# RS485_RS232_Sheet.net
KiCad netlist of a schematic drawn in Altium Designer
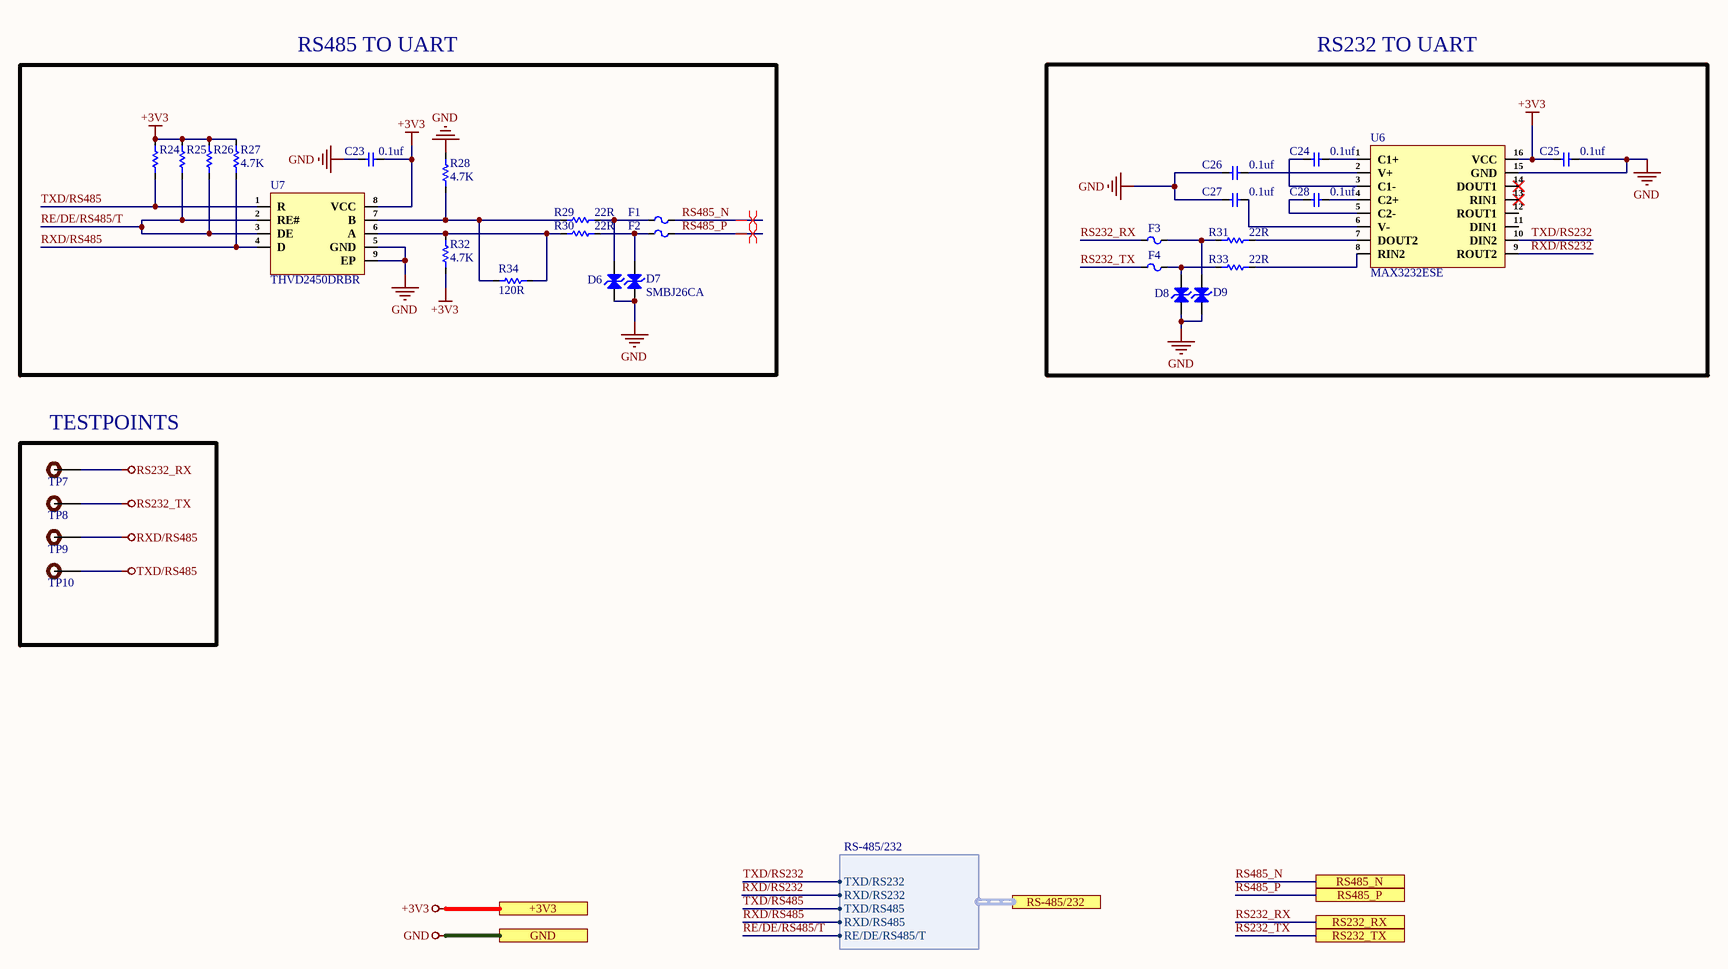
[diagram p0: RS485_RS232_Sheet.SchDoc]

(export (version "E")
  (design (tool "Eeschema 10.0.6"))
  (components
    (comp (ref "C23")
      (value "0.1uf")
      (footprint "Cap-0402")
      (description "CAP CER 0.1UF 100V X5R 0402")
      (fields
        (field (name "MANUFACTURER") "Murata")
        (field (name "MANUFACTURER PART NUMBER") "GRM155R62A104KE14D")
      )
      (libsource (lib "eSpark Libraries") (part "GRM155R62A104KE14D"))
    )
    (comp (ref "C24")
      (value "0.1uf")
      (footprint "Cap-0402")
      (description "CAP CER 0.1UF 100V X5R 0402")
      (fields
        (field (name "MANUFACTURER") "Murata")
        (field (name "MANUFACTURER PART NUMBER") "GRM155R62A104KE14D")
      )
      (libsource (lib "eSpark Libraries") (part "GRM155R62A104KE14D"))
    )
    (comp (ref "C25")
      (value "0.1uf")
      (footprint "Cap-0402")
      (description "CAP CER 0.1UF 100V X5R 0402")
      (fields
        (field (name "MANUFACTURER") "Murata")
        (field (name "MANUFACTURER PART NUMBER") "GRM155R62A104KE14D")
      )
      (libsource (lib "eSpark Libraries") (part "GRM155R62A104KE14D"))
    )
    (comp (ref "C26")
      (value "0.1uf")
      (footprint "Cap-0402")
      (description "CAP CER 0.1UF 100V X5R 0402")
      (fields
        (field (name "MANUFACTURER") "Murata")
        (field (name "MANUFACTURER PART NUMBER") "GRM155R62A104KE14D")
      )
      (libsource (lib "eSpark Libraries") (part "GRM155R62A104KE14D"))
    )
    (comp (ref "C27")
      (value "0.1uf")
      (footprint "Cap-0402")
      (description "CAP CER 0.1UF 100V X5R 0402")
      (fields
        (field (name "MANUFACTURER") "Murata")
        (field (name "MANUFACTURER PART NUMBER") "GRM155R62A104KE14D")
      )
      (libsource (lib "eSpark Libraries") (part "GRM155R62A104KE14D"))
    )
    (comp (ref "C28")
      (value "0.1uf")
      (footprint "Cap-0402")
      (description "CAP CER 0.1UF 100V X5R 0402")
      (fields
        (field (name "MANUFACTURER") "Murata")
        (field (name "MANUFACTURER PART NUMBER") "GRM155R62A104KE14D")
      )
      (libsource (lib "eSpark Libraries") (part "GRM155R62A104KE14D"))
    )
    (comp (ref "D6")
      (value "SMBJ26CA")
      (footprint "SMB Bi Directional")
      (description "SMB(DO-214AA) TVS ROHS")
      (fields (field (name "MANUFACTURER") "MSKSEMI") (field (name "LCSC PART NUMBER") "C5331111"))
      (libsource (lib "eSpark Libraries") (part "SMBJ26CA"))
    )
    (comp (ref "D7")
      (value "SMBJ26CA")
      (footprint "SMB Bi Directional")
      (description "SMB(DO-214AA) TVS ROHS")
      (fields (field (name "MANUFACTURER") "MSKSEMI") (field (name "LCSC PART NUMBER") "C5331111"))
      (libsource (lib "eSpark Libraries") (part "SMBJ26CA"))
    )
    (comp (ref "D8")
      (value "SMBJ26CA")
      (footprint "SMB Bi Directional")
      (description "SMB(DO-214AA) TVS ROHS")
      (fields (field (name "MANUFACTURER") "MSKSEMI") (field (name "LCSC PART NUMBER") "C5331111"))
      (libsource (lib "eSpark Libraries") (part "SMBJ26CA"))
    )
    (comp (ref "D9")
      (value "SMBJ26CA")
      (footprint "SMB Bi Directional")
      (description "SMB(DO-214AA) TVS ROHS")
      (fields (field (name "MANUFACTURER") "MSKSEMI") (field (name "LCSC PART NUMBER") "C5331111"))
      (libsource (lib "eSpark Libraries") (part "SMBJ26CA"))
    )
    (comp (ref "F1")
      (value "SMD0805P020TF")
      (footprint "Fuse-0805")
      (description "9V 200mA 100A 500mA 0805 Resettable Fuses ROHS")
      (fields (field (name "MANUFACTURER") "RUILON") (field (name "LCSC PART NUMBER") "C20976"))
      (libsource (lib "eSpark_centralized_Library(2022)") (part "SMD0805P020TF"))
    )
    (comp (ref "F2")
      (value "SMD0805P020TF")
      (footprint "Fuse-0805")
      (description "9V 200mA 100A 500mA 0805 Resettable Fuses ROHS")
      (fields (field (name "MANUFACTURER") "RUILON") (field (name "LCSC PART NUMBER") "C20976"))
      (libsource (lib "eSpark_centralized_Library(2022)") (part "SMD0805P020TF"))
    )
    (comp (ref "F3")
      (value "SMD0805P020TF")
      (footprint "Fuse-0805")
      (description "9V 200mA 100A 500mA 0805 Resettable Fuses ROHS")
      (fields (field (name "MANUFACTURER") "RUILON") (field (name "LCSC PART NUMBER") "C20976"))
      (libsource (lib "eSpark Libraries") (part "SMD0805P020TF"))
    )
    (comp (ref "F4")
      (value "SMD0805P020TF")
      (footprint "Fuse-0805")
      (description "9V 200mA 100A 500mA 0805 Resettable Fuses ROHS")
      (fields (field (name "MANUFACTURER") "RUILON") (field (name "LCSC PART NUMBER") "C20976"))
      (libsource (lib "eSpark Libraries") (part "SMD0805P020TF"))
    )
    (comp (ref "R24")
      (value "4.7K")
      (footprint "Res-0402")
      (description "RES 4.7K OHM 1% 1/16W 0402")
      (fields
        (field (name "MANUFACTURER") "Yageo")
        (field (name "MANUFACTURER PART NUMBER") "RC0402FR-074K7L")
      )
      (libsource (lib "eSpark Libraries") (part "RC0402FR-074K7L"))
    )
    (comp (ref "R25")
      (value "4.7K")
      (footprint "Res-0402")
      (description "RES 4.7K OHM 1% 1/16W 0402")
      (fields
        (field (name "MANUFACTURER") "Yageo")
        (field (name "MANUFACTURER PART NUMBER") "RC0402FR-074K7L")
      )
      (libsource (lib "eSpark Libraries") (part "RC0402FR-074K7L"))
    )
    (comp (ref "R26")
      (value "4.7K")
      (footprint "Res-0402")
      (description "RES 4.7K OHM 1% 1/16W 0402")
      (fields
        (field (name "MANUFACTURER") "Yageo")
        (field (name "MANUFACTURER PART NUMBER") "RC0402FR-074K7L")
      )
      (libsource (lib "eSpark Libraries") (part "RC0402FR-074K7L"))
    )
    (comp (ref "R27")
      (value "4.7K")
      (footprint "Res-0402")
      (description "RES 4.7K OHM 1% 1/16W 0402")
      (fields
        (field (name "MANUFACTURER") "Yageo")
        (field (name "MANUFACTURER PART NUMBER") "RC0402FR-074K7L")
      )
      (libsource (lib "eSpark Libraries") (part "RC0402FR-074K7L"))
    )
    (comp (ref "R28")
      (value "4.7K")
      (footprint "Res-0402")
      (description "RES 4.7K OHM 1% 1/16W 0402")
      (fields
        (field (name "MANUFACTURER") "Yageo")
        (field (name "MANUFACTURER PART NUMBER") "RC0402FR-074K7L")
      )
      (libsource (lib "eSpark Libraries") (part "RC0402FR-074K7L"))
    )
    (comp (ref "R29")
      (value "22R")
      (footprint "Res-0201")
      (description "RES 22 OHM 1% 1/20W 0201")
      (fields
        (field (name "MANUFACTURER") "Yageo")
        (field (name "MANUFACTURER PART NUMBER") "RC0201FR-0722RL")
      )
      (libsource (lib "eSpark Libraries") (part "RC0201FR-0722RL"))
    )
    (comp (ref "R30")
      (value "22R")
      (footprint "Res-0201")
      (description "RES 22 OHM 1% 1/20W 0201")
      (fields
        (field (name "MANUFACTURER") "Yageo")
        (field (name "MANUFACTURER PART NUMBER") "RC0201FR-0722RL")
      )
      (libsource (lib "eSpark Libraries") (part "RC0201FR-0722RL"))
    )
    (comp (ref "R31")
      (value "22R")
      (footprint "Res-0201")
      (description "RES 22 OHM 1% 1/20W 0201")
      (fields
        (field (name "MANUFACTURER") "Yageo")
        (field (name "MANUFACTURER PART NUMBER") "RC0201FR-0722RL")
      )
      (libsource (lib "eSpark Libraries") (part "RC0201FR-0722RL"))
    )
    (comp (ref "R32")
      (value "4.7K")
      (footprint "Res-0402")
      (description "RES 4.7K OHM 1% 1/16W 0402")
      (fields
        (field (name "MANUFACTURER") "Yageo")
        (field (name "MANUFACTURER PART NUMBER") "RC0402FR-074K7L")
      )
      (libsource (lib "eSpark Libraries") (part "RC0402FR-074K7L"))
    )
    (comp (ref "R33")
      (value "22R")
      (footprint "Res-0201")
      (description "RES 22 OHM 1% 1/20W 0201")
      (fields
        (field (name "MANUFACTURER") "Yageo")
        (field (name "MANUFACTURER PART NUMBER") "RC0201FR-0722RL")
      )
      (libsource (lib "eSpark Libraries") (part "RC0201FR-0722RL"))
    )
    (comp (ref "R34")
      (value "120R")
      (footprint "Res-0603")
      (description "RES 120 OHM 5% 1/10W 0603")
      (fields
        (field (name "MANUFACTURER") "Yageo")
        (field (name "MANUFACTURER PART NUMBER") "RC0603JR-07120RL")
      )
      (libsource (lib "eSpark Libraries") (part "RC0603JR-07120RL"))
    )
    (comp (ref "TP7")
      (value "TEST POINT")
      (footprint "Test-point")
      (description "Test Point ON")
      (libsource (lib "eSpark Libraries") (part "TEST POINT"))
    )
    (comp (ref "TP8")
      (value "TEST POINT")
      (footprint "Test-point")
      (description "Test Point ON")
      (libsource (lib "eSpark Libraries") (part "TEST POINT"))
    )
    (comp (ref "TP9")
      (value "TEST POINT")
      (footprint "Test-point")
      (description "Test Point ON")
      (libsource (lib "eSpark Libraries") (part "TEST POINT"))
    )
    (comp (ref "TP10")
      (value "TEST POINT")
      (footprint "Test-point")
      (description "Test Point ON")
      (libsource (lib "eSpark Libraries") (part "TEST POINT"))
    )
    (comp (ref "U6")
      (value "MAX3232ESE")
      (footprint "SOP-16")
      (description "250Kbps transceiver 2/2 SOP-16 RS232 ICs ROHS")
      (fields (field (name "MANUFACTURER") "UMW") (field (name "LCSC PART NUMBER") "C2904738"))
      (libsource (lib "eSpark Libraries") (part "MAX3232ESE"))
    )
    (comp (ref "U7")
      (value "THVD2450DRBR")
      (footprint "SON-8-EP(3x3)")
      (description "IC TRANSCEIVER HALF 1/1 8SON")
      (fields (field (name "MANUFACTURER") "Texas Instruments") (field (name "LCSC PART NUMBER") "C2878080"))
      (libsource (lib "eSpark Libraries") (part "THVD2450DRBR"))
    )
  )
  (nets
    (net (code "2") (name "+3V3") (class "Default")
      (node (ref "C23") (pin "2") (pinfunction "2_2") (pintype "passive"))
      (node (ref "C25") (pin "2") (pinfunction "2_2") (pintype "passive"))
      (node (ref "R24") (pin "2") (pinfunction "2_2") (pintype "passive"))
      (node (ref "R25") (pin "2") (pinfunction "2_2") (pintype "passive"))
      (node (ref "R26") (pin "2") (pinfunction "2_2") (pintype "passive"))
      (node (ref "R27") (pin "2") (pinfunction "2_2") (pintype "passive"))
      (node (ref "R32") (pin "1") (pinfunction "1_1") (pintype "passive"))
      (node (ref "U6") (pin "16") (pinfunction "VCC_16") (pintype "passive"))
      (node (ref "U7") (pin "8") (pinfunction "VCC_8") (pintype "passive"))
    )
    (net (code "3") (name "/RE{slash}DE{slash}RS485{slash}T") (class "Default")
      (node (ref "R25") (pin "1") (pinfunction "1_1") (pintype "passive"))
      (node (ref "R26") (pin "1") (pinfunction "1_1") (pintype "passive"))
      (node (ref "U7") (pin "2") (pinfunction "RE#_2") (pintype "passive"))
      (node (ref "U7") (pin "3") (pinfunction "DE_3") (pintype "passive"))
    )
    (net (code "4") (name "/RS485_N") (class "Default")
      (node (ref "F1") (pin "2") (pinfunction "2_2") (pintype "passive"))
    )
    (net (code "5") (name "/RS485_P") (class "Default")
      (node (ref "F2") (pin "2") (pinfunction "2_2") (pintype "passive"))
    )
    (net (code "6") (name "/RXD{slash}RS232") (class "Default")
      (node (ref "U6") (pin "9") (pinfunction "ROUT2_9") (pintype "passive"))
    )
    (net (code "7") (name "/TXD{slash}RS232") (class "Default")
      (node (ref "U6") (pin "10") (pinfunction "DIN2_10") (pintype "passive"))
    )
    (net (code "9") (name "GND") (class "Default")
      (node (ref "C23") (pin "1") (pinfunction "1_1") (pintype "passive"))
      (node (ref "C25") (pin "1") (pinfunction "1_1") (pintype "passive"))
      (node (ref "C26") (pin "1") (pinfunction "1_1") (pintype "passive"))
      (node (ref "C27") (pin "1") (pinfunction "1_1") (pintype "passive"))
      (node (ref "D6") (pin "1") (pinfunction "A_1") (pintype "passive"))
      (node (ref "D7") (pin "1") (pinfunction "A_1") (pintype "passive"))
      (node (ref "D8") (pin "1") (pinfunction "A_1") (pintype "passive"))
      (node (ref "D9") (pin "1") (pinfunction "A_1") (pintype "passive"))
      (node (ref "R28") (pin "2") (pinfunction "2_2") (pintype "passive"))
      (node (ref "U6") (pin "15") (pinfunction "GND_15") (pintype "passive"))
      (node (ref "U7") (pin "5") (pinfunction "GND_5") (pintype "passive"))
      (node (ref "U7") (pin "9") (pinfunction "EP_9") (pintype "passive"))
    )
    (net (code "10") (name "Net-(D6-K)") (class "Default")
      (node (ref "D6") (pin "2") (pinfunction "K_2") (pintype "passive"))
      (node (ref "F1") (pin "1") (pinfunction "1_1") (pintype "passive"))
      (node (ref "R29") (pin "2") (pinfunction "2_2") (pintype "passive"))
    )
    (net (code "11") (name "Net-(D7-K)") (class "Default")
      (node (ref "D7") (pin "2") (pinfunction "K_2") (pintype "passive"))
      (node (ref "F2") (pin "1") (pinfunction "1_1") (pintype "passive"))
      (node (ref "R30") (pin "2") (pinfunction "2_2") (pintype "passive"))
    )
    (net (code "12") (name "Net-(D8-K)") (class "Default")
      (node (ref "D8") (pin "2") (pinfunction "K_2") (pintype "passive"))
      (node (ref "F4") (pin "2") (pinfunction "2_2") (pintype "passive"))
      (node (ref "R33") (pin "1") (pinfunction "1_1") (pintype "passive"))
    )
    (net (code "13") (name "Net-(D9-K)") (class "Default")
      (node (ref "D9") (pin "2") (pinfunction "K_2") (pintype "passive"))
      (node (ref "F3") (pin "2") (pinfunction "2_2") (pintype "passive"))
      (node (ref "R31") (pin "1") (pinfunction "1_1") (pintype "passive"))
    )
    (net (code "14") (name "Net-(U6-C1+)") (class "Default")
      (node (ref "C24") (pin "1") (pinfunction "1_1") (pintype "passive"))
      (node (ref "U6") (pin "1") (pinfunction "C1+_1") (pintype "passive"))
    )
    (net (code "15") (name "Net-(U6-C1-)") (class "Default")
      (node (ref "C24") (pin "2") (pinfunction "2_2") (pintype "passive"))
      (node (ref "U6") (pin "3") (pinfunction "C1-_3") (pintype "passive"))
    )
    (net (code "16") (name "Net-(U6-C2+)") (class "Default")
      (node (ref "C28") (pin "1") (pinfunction "1_1") (pintype "passive"))
      (node (ref "U6") (pin "4") (pinfunction "C2+_4") (pintype "passive"))
    )
    (net (code "17") (name "Net-(U6-C2-)") (class "Default")
      (node (ref "C28") (pin "2") (pinfunction "2_2") (pintype "passive"))
      (node (ref "U6") (pin "5") (pinfunction "C2-_5") (pintype "passive"))
    )
    (net (code "18") (name "Net-(U6-DOUT2)") (class "Default")
      (node (ref "R31") (pin "2") (pinfunction "2_2") (pintype "passive"))
      (node (ref "U6") (pin "7") (pinfunction "DOUT2_7") (pintype "passive"))
    )
    (net (code "19") (name "Net-(U6-RIN2)") (class "Default")
      (node (ref "R33") (pin "2") (pinfunction "2_2") (pintype "passive"))
      (node (ref "U6") (pin "8") (pinfunction "RIN2_8") (pintype "passive"))
    )
    (net (code "20") (name "Net-(U6-V+)") (class "Default")
      (node (ref "C26") (pin "2") (pinfunction "2_2") (pintype "passive"))
      (node (ref "U6") (pin "2") (pinfunction "V+_2") (pintype "passive"))
    )
    (net (code "21") (name "Net-(U6-V-)") (class "Default")
      (node (ref "C27") (pin "2") (pinfunction "2_2") (pintype "passive"))
      (node (ref "U6") (pin "6") (pinfunction "V-_6") (pintype "passive"))
    )
    (net (code "22") (name "Net-(U7-A)") (class "Default")
      (node (ref "R30") (pin "1") (pinfunction "1_1") (pintype "passive"))
      (node (ref "R32") (pin "2") (pinfunction "2_2") (pintype "passive"))
      (node (ref "R34") (pin "2") (pinfunction "2_2") (pintype "passive"))
      (node (ref "U7") (pin "6") (pinfunction "A_6") (pintype "passive"))
    )
    (net (code "23") (name "Net-(U7-B)") (class "Default")
      (node (ref "R28") (pin "1") (pinfunction "1_1") (pintype "passive"))
      (node (ref "R29") (pin "1") (pinfunction "1_1") (pintype "passive"))
      (node (ref "R34") (pin "1") (pinfunction "1_1") (pintype "passive"))
      (node (ref "U7") (pin "7") (pinfunction "B_7") (pintype "passive"))
    )
    (net (code "24") (name "RS232_RX") (class "Default")
      (node (ref "F3") (pin "1") (pinfunction "1_1") (pintype "passive"))
      (node (ref "TP7") (pin "1") (pinfunction "1_1") (pintype "passive"))
    )
    (net (code "25") (name "RS232_TX") (class "Default")
      (node (ref "F4") (pin "1") (pinfunction "1_1") (pintype "passive"))
      (node (ref "TP8") (pin "1") (pinfunction "1_1") (pintype "passive"))
    )
    (net (code "26") (name "RXD{slash}RS485") (class "Default")
      (node (ref "R27") (pin "1") (pinfunction "1_1") (pintype "passive"))
      (node (ref "TP9") (pin "1") (pinfunction "1_1") (pintype "passive"))
      (node (ref "U7") (pin "4") (pinfunction "D_4") (pintype "passive"))
    )
    (net (code "27") (name "TXD{slash}RS485") (class "Default")
      (node (ref "R24") (pin "1") (pinfunction "1_1") (pintype "passive"))
      (node (ref "TP10") (pin "1") (pinfunction "1_1") (pintype "passive"))
      (node (ref "U7") (pin "1") (pinfunction "R_1") (pintype "passive"))
    )
    (net (code "28") (name "unconnected-(U6-DIN1-Pad11)") (class "Default")
      (node (ref "U6") (pin "11") (pinfunction "DIN1_11") (pintype "passive"))
    )
    (net (code "29") (name "unconnected-(U6-DOUT1-Pad14)") (class "Default")
      (node (ref "U6") (pin "14") (pinfunction "DOUT1_14") (pintype "passive+no_connect"))
    )
    (net (code "30") (name "unconnected-(U6-RIN1-Pad13)") (class "Default")
      (node (ref "U6") (pin "13") (pinfunction "RIN1_13") (pintype "passive+no_connect"))
    )
    (net (code "31") (name "unconnected-(U6-ROUT1-Pad12)") (class "Default")
      (node (ref "U6") (pin "12") (pinfunction "ROUT1_12") (pintype "passive"))
    )
  )
)
